# sd_tos.net
KiCad netlist of a schematic drawn in EAGLE
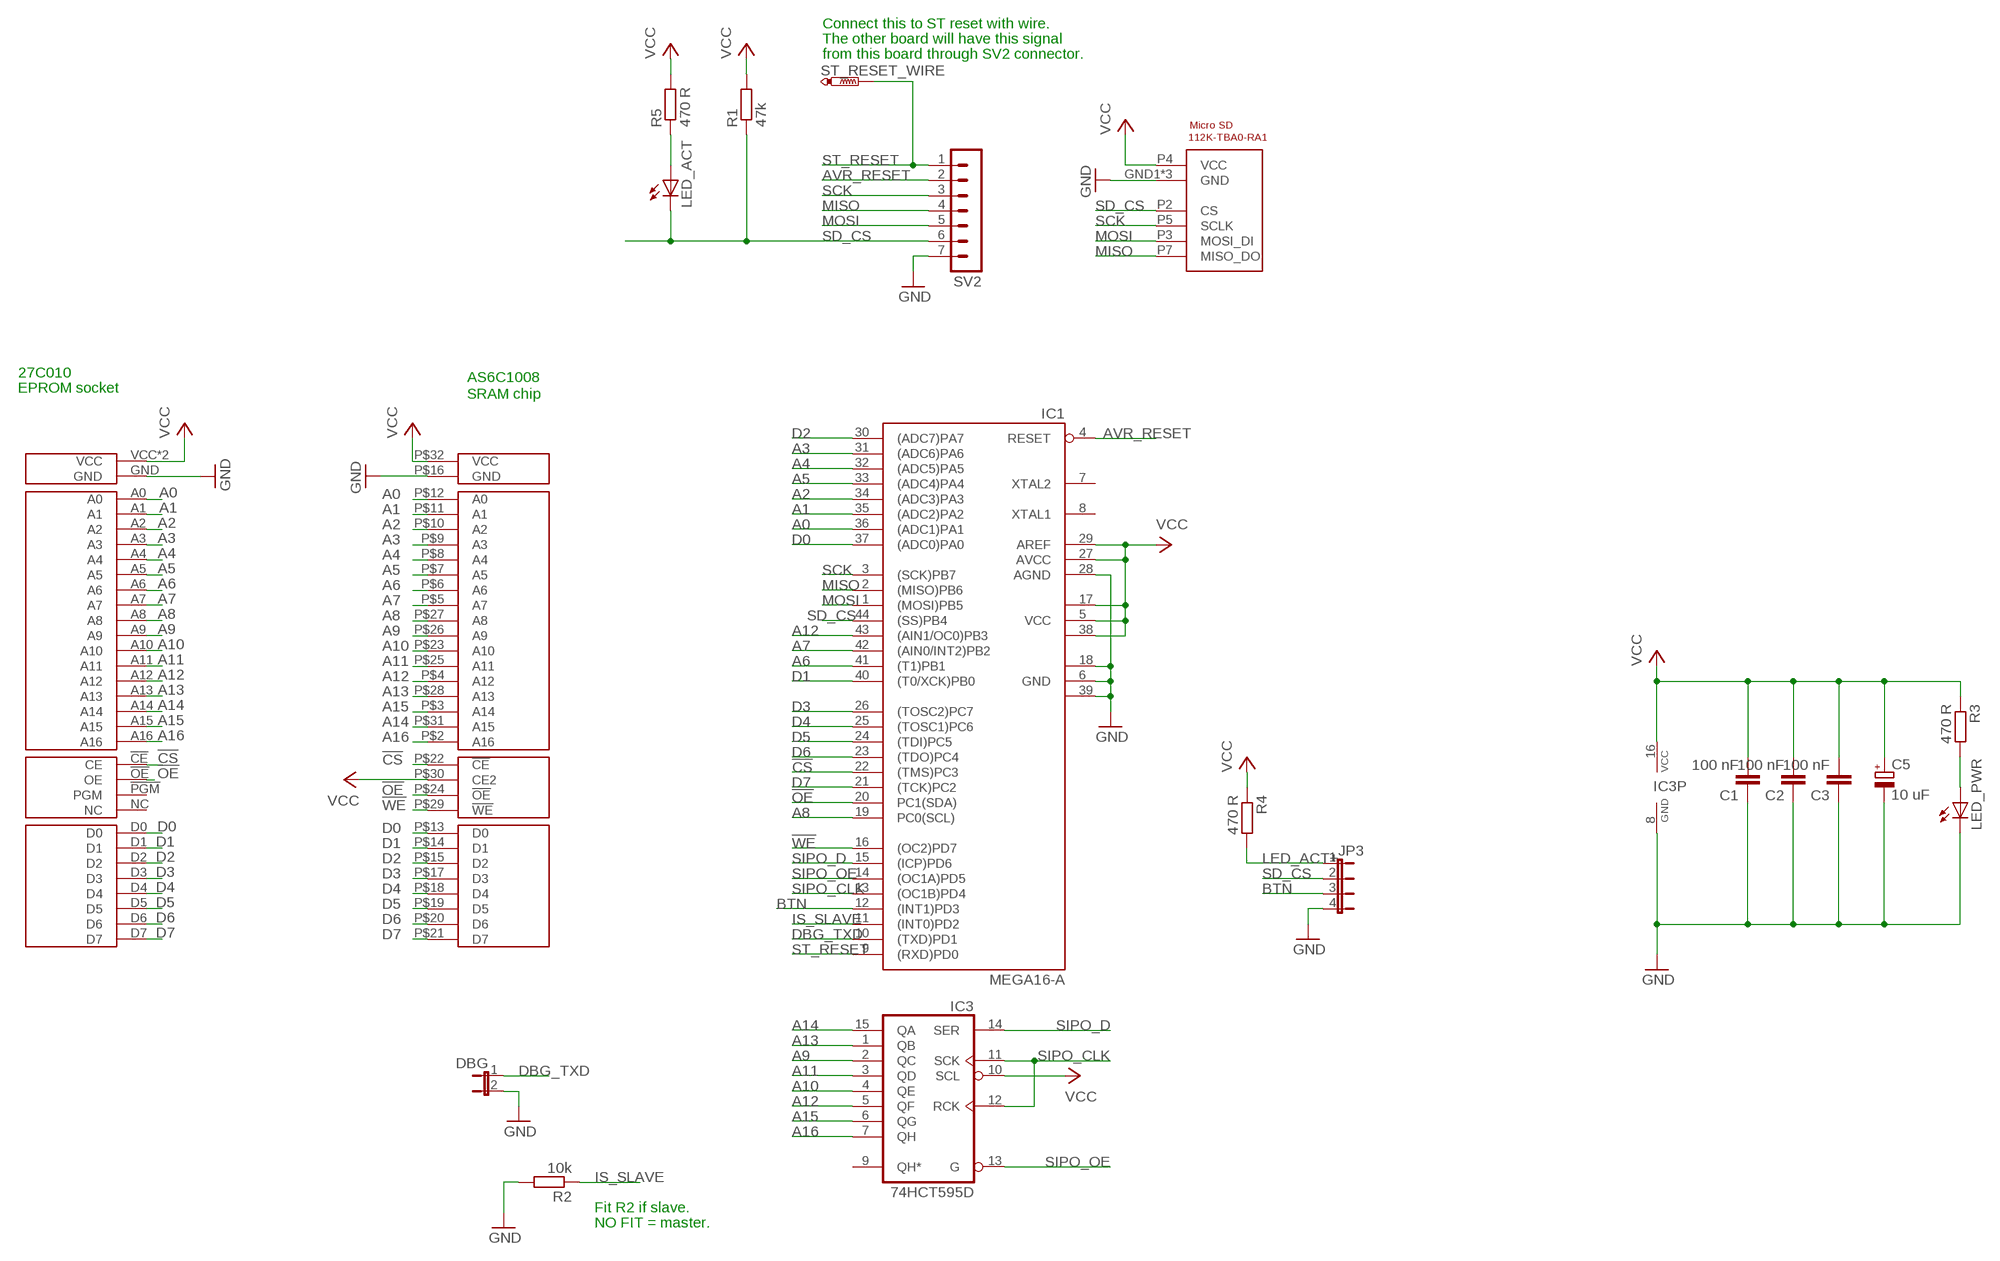
[diagram p0: schematic, sheet 1]

(export (version "E")
  (design (tool "Eeschema 10.0.6"))
  (components
    (comp (ref "C1")
      (value "100 nF")
      (footprint "eagle-import:C0603")
      (libsource (lib "eagle-import") (part "C-EUC0603"))
    )
    (comp (ref "C2")
      (value "100 nF")
      (footprint "eagle-import:C0603")
      (libsource (lib "eagle-import") (part "C-EUC0603"))
    )
    (comp (ref "C3")
      (value "100 nF")
      (footprint "eagle-import:C0603")
      (libsource (lib "eagle-import") (part "C-EUC0603"))
    )
    (comp (ref "C5")
      (value "10 uF")
      (footprint "eagle-import:SANYO-OSCON_SMD_B6")
      (libsource (lib "eagle-import") (part "CPOL-EUSANYO_SMD_B6"))
    )
    (comp (ref "DBG")
      (value "JP1E")
      (footprint "eagle-import:JP1")
      (libsource (lib "eagle-import") (part "JP1E"))
    )
    (comp (ref "IC1")
      (value "MEGA16-A")
      (footprint "eagle-import:TQFP44")
      (libsource (lib "eagle-import") (part "MEGA16-A"))
    )
    (comp (ref "IC3")
      (value "74HCT595D")
      (footprint "eagle-import:SO16")
      (libsource (lib "eagle-import") (part "74595DHCT"))
    )
    (comp (ref "JP3")
      (value "JP4E")
      (footprint "eagle-import:JP4")
      (libsource (lib "eagle-import") (part "JP4E"))
    )
    (comp (ref "LED_ACT")
      (value "LEDCHIP-LED0805")
      (footprint "eagle-import:CHIP-LED0805")
      (libsource (lib "eagle-import") (part "LEDCHIP-LED0805"))
    )
    (comp (ref "LED_PWR")
      (value "LEDCHIP-LED0805")
      (footprint "eagle-import:CHIP-LED0805")
      (libsource (lib "eagle-import") (part "LEDCHIP-LED0805"))
    )
    (comp (ref "R1")
      (value "47k")
      (footprint "eagle-import:R0603")
      (libsource (lib "eagle-import") (part "R-EU_R0603"))
    )
    (comp (ref "R2")
      (value "10k")
      (footprint "eagle-import:R0603")
      (libsource (lib "eagle-import") (part "R-EU_R0603"))
    )
    (comp (ref "R3")
      (value "470 R")
      (footprint "eagle-import:R0603")
      (libsource (lib "eagle-import") (part "R-EU_R0603"))
    )
    (comp (ref "R4")
      (value "470 R")
      (footprint "eagle-import:R0603")
      (libsource (lib "eagle-import") (part "R-EU_R0603"))
    )
    (comp (ref "R5")
      (value "470 R")
      (footprint "eagle-import:R0603")
      (libsource (lib "eagle-import") (part "R-EU_R0603"))
    )
    (comp (ref "ST_RESET_WIRE")
      (value "PTR1PAD1-13Y")
      (footprint "eagle-import:P1-13Y")
      (libsource (lib "eagle-import") (part "PTR1PAD1-13Y"))
    )
    (comp (ref "SV2")
      (value "MA07-1")
      (footprint "eagle-import:MA07-1")
      (libsource (lib "eagle-import") (part "MA07-1"))
    )
    (comp (ref "U$1")
      (value "27C010_BOTTOM_ONLY")
      (footprint "eagle-import:DIP32_BOTTOM_ONLY")
      (libsource (lib "eagle-import") (part "27C010_BOTTOM_ONLY"))
    )
    (comp (ref "U$2")
      (value "AS6C1008")
      (footprint "eagle-import:SOP32L")
      (libsource (lib "eagle-import") (part "AS6C1008"))
    )
    (comp (ref "U$3")
      (value "MICRO_SD")
      (footprint "eagle-import:MICRO_SD")
      (libsource (lib "eagle-import") (part "MICRO_SD"))
    )
  )
  (nets
    (net (code "1") (name "/A0") (class "Default")
      (node (ref "IC1") (pin "36") (pinfunction "(ADC1)PA1_36") (pintype "bidirectional"))
      (node (ref "U$1") (pin "A0") (pinfunction "A0_A0") (pintype "bidirectional"))
      (node (ref "U$2") (pin "P$12") (pinfunction "A0_P$12") (pintype "bidirectional"))
    )
    (net (code "2") (name "/A1") (class "Default")
      (node (ref "IC1") (pin "35") (pinfunction "(ADC2)PA2_35") (pintype "bidirectional"))
      (node (ref "U$1") (pin "A1") (pinfunction "A1_A1") (pintype "bidirectional"))
      (node (ref "U$2") (pin "P$11") (pinfunction "A1_P$11") (pintype "bidirectional"))
    )
    (net (code "3") (name "/A2") (class "Default")
      (node (ref "IC1") (pin "34") (pinfunction "(ADC3)PA3_34") (pintype "bidirectional"))
      (node (ref "U$1") (pin "A2") (pinfunction "A2_A2") (pintype "bidirectional"))
      (node (ref "U$2") (pin "P$10") (pinfunction "A2_P$10") (pintype "bidirectional"))
    )
    (net (code "4") (name "/A3") (class "Default")
      (node (ref "IC1") (pin "31") (pinfunction "(ADC6)PA6_31") (pintype "bidirectional"))
      (node (ref "U$1") (pin "A3") (pinfunction "A3_A3") (pintype "bidirectional"))
      (node (ref "U$2") (pin "P$9") (pinfunction "A3_P$9") (pintype "bidirectional"))
    )
    (net (code "5") (name "/A4") (class "Default")
      (node (ref "IC1") (pin "32") (pinfunction "(ADC5)PA5_32") (pintype "bidirectional"))
      (node (ref "U$1") (pin "A4") (pinfunction "A4_A4") (pintype "bidirectional"))
      (node (ref "U$2") (pin "P$8") (pinfunction "A4_P$8") (pintype "bidirectional"))
    )
    (net (code "6") (name "/A5") (class "Default")
      (node (ref "IC1") (pin "33") (pinfunction "(ADC4)PA4_33") (pintype "bidirectional"))
      (node (ref "U$1") (pin "A5") (pinfunction "A5_A5") (pintype "bidirectional"))
      (node (ref "U$2") (pin "P$7") (pinfunction "A5_P$7") (pintype "bidirectional"))
    )
    (net (code "7") (name "/A6") (class "Default")
      (node (ref "IC1") (pin "41") (pinfunction "(T1)PB1_41") (pintype "bidirectional"))
      (node (ref "U$1") (pin "A6") (pinfunction "A6_A6") (pintype "bidirectional"))
      (node (ref "U$2") (pin "P$6") (pinfunction "A6_P$6") (pintype "bidirectional"))
    )
    (net (code "8") (name "/A7") (class "Default")
      (node (ref "IC1") (pin "42") (pinfunction "(AIN0/INT2)PB2_42") (pintype "bidirectional"))
      (node (ref "U$1") (pin "A7") (pinfunction "A7_A7") (pintype "bidirectional"))
      (node (ref "U$2") (pin "P$5") (pinfunction "A7_P$5") (pintype "bidirectional"))
    )
    (net (code "9") (name "/A8") (class "Default")
      (node (ref "IC1") (pin "19") (pinfunction "PC0(SCL)_19") (pintype "bidirectional"))
      (node (ref "U$1") (pin "A8") (pinfunction "A8_A8") (pintype "bidirectional"))
      (node (ref "U$2") (pin "P$27") (pinfunction "A8_P$27") (pintype "bidirectional"))
    )
    (net (code "10") (name "/A9") (class "Default")
      (node (ref "IC3") (pin "2") (pinfunction "QC_2") (pintype "tri_state"))
      (node (ref "U$1") (pin "A9") (pinfunction "A9_A9") (pintype "bidirectional"))
      (node (ref "U$2") (pin "P$26") (pinfunction "A9_P$26") (pintype "bidirectional"))
    )
    (net (code "11") (name "/A10") (class "Default")
      (node (ref "IC3") (pin "4") (pinfunction "QE_4") (pintype "tri_state"))
      (node (ref "U$1") (pin "A10") (pinfunction "A10_A10") (pintype "bidirectional"))
      (node (ref "U$2") (pin "P$23") (pinfunction "A10_P$23") (pintype "bidirectional"))
    )
    (net (code "12") (name "/A11") (class "Default")
      (node (ref "IC3") (pin "3") (pinfunction "QD_3") (pintype "tri_state"))
      (node (ref "U$1") (pin "A11") (pinfunction "A11_A11") (pintype "bidirectional"))
      (node (ref "U$2") (pin "P$25") (pinfunction "A11_P$25") (pintype "bidirectional"))
    )
    (net (code "13") (name "/A12") (class "Default")
      (node (ref "IC1") (pin "43") (pinfunction "(AIN1/OC0)PB3_43") (pintype "bidirectional"))
      (node (ref "IC3") (pin "5") (pinfunction "QF_5") (pintype "tri_state"))
      (node (ref "U$1") (pin "A12") (pinfunction "A12_A12") (pintype "bidirectional"))
      (node (ref "U$2") (pin "P$4") (pinfunction "A12_P$4") (pintype "bidirectional"))
    )
    (net (code "14") (name "/A13") (class "Default")
      (node (ref "IC3") (pin "1") (pinfunction "QB_1") (pintype "tri_state"))
      (node (ref "U$1") (pin "A13") (pinfunction "A13_A13") (pintype "bidirectional"))
      (node (ref "U$2") (pin "P$28") (pinfunction "A13_P$28") (pintype "bidirectional"))
    )
    (net (code "15") (name "/A14") (class "Default")
      (node (ref "IC3") (pin "15") (pinfunction "QA_15") (pintype "tri_state"))
      (node (ref "U$1") (pin "A14") (pinfunction "A14_A14") (pintype "bidirectional"))
      (node (ref "U$2") (pin "P$31") (pinfunction "A15_P$31") (pintype "bidirectional"))
    )
    (net (code "16") (name "/A15") (class "Default")
      (node (ref "IC3") (pin "6") (pinfunction "QG_6") (pintype "tri_state"))
      (node (ref "U$1") (pin "A15") (pinfunction "A15_A15") (pintype "bidirectional"))
      (node (ref "U$2") (pin "P$3") (pinfunction "A14_P$3") (pintype "bidirectional"))
    )
    (net (code "17") (name "/A16") (class "Default")
      (node (ref "IC3") (pin "7") (pinfunction "QH_7") (pintype "tri_state"))
      (node (ref "U$1") (pin "A16") (pinfunction "A16_A16") (pintype "bidirectional"))
      (node (ref "U$2") (pin "P$2") (pinfunction "A16_P$2") (pintype "bidirectional"))
    )
    (net (code "18") (name "/AVR_RESET") (class "Default")
      (node (ref "IC1") (pin "4") (pinfunction "RESET_4") (pintype "input"))
      (node (ref "SV2") (pin "2") (pinfunction "2_2") (pintype "passive"))
    )
    (net (code "19") (name "/BTN") (class "Default")
      (node (ref "IC1") (pin "12") (pinfunction "(INT1)PD3_12") (pintype "bidirectional"))
      (node (ref "JP3") (pin "3") (pinfunction "3_3") (pintype "passive"))
    )
    (net (code "20") (name "/D0") (class "Default")
      (node (ref "IC1") (pin "37") (pinfunction "(ADC0)PA0_37") (pintype "bidirectional"))
      (node (ref "U$1") (pin "D0") (pinfunction "D0_D0") (pintype "bidirectional"))
      (node (ref "U$2") (pin "P$13") (pinfunction "D0_P$13") (pintype "bidirectional"))
    )
    (net (code "21") (name "/D1") (class "Default")
      (node (ref "IC1") (pin "40") (pinfunction "(T0/XCK)PB0_40") (pintype "bidirectional"))
      (node (ref "U$1") (pin "D1") (pinfunction "D1_D1") (pintype "bidirectional"))
      (node (ref "U$2") (pin "P$14") (pinfunction "D1_P$14") (pintype "bidirectional"))
    )
    (net (code "22") (name "/D2") (class "Default")
      (node (ref "IC1") (pin "30") (pinfunction "(ADC7)PA7_30") (pintype "bidirectional"))
      (node (ref "U$1") (pin "D2") (pinfunction "D2_D2") (pintype "bidirectional"))
      (node (ref "U$2") (pin "P$15") (pinfunction "D2_P$15") (pintype "bidirectional"))
    )
    (net (code "23") (name "/D3") (class "Default")
      (node (ref "IC1") (pin "26") (pinfunction "(TOSC2)PC7_26") (pintype "bidirectional"))
      (node (ref "U$1") (pin "D3") (pinfunction "D3_D3") (pintype "bidirectional"))
      (node (ref "U$2") (pin "P$17") (pinfunction "D3_P$17") (pintype "bidirectional"))
    )
    (net (code "24") (name "/D4") (class "Default")
      (node (ref "IC1") (pin "25") (pinfunction "(TOSC1)PC6_25") (pintype "bidirectional"))
      (node (ref "U$1") (pin "D4") (pinfunction "D4_D4") (pintype "bidirectional"))
      (node (ref "U$2") (pin "P$18") (pinfunction "D4_P$18") (pintype "bidirectional"))
    )
    (net (code "25") (name "/D5") (class "Default")
      (node (ref "IC1") (pin "24") (pinfunction "(TDI)PC5_24") (pintype "bidirectional"))
      (node (ref "U$1") (pin "D5") (pinfunction "D5_D5") (pintype "bidirectional"))
      (node (ref "U$2") (pin "P$19") (pinfunction "D5_P$19") (pintype "bidirectional"))
    )
    (net (code "26") (name "/D6") (class "Default")
      (node (ref "IC1") (pin "23") (pinfunction "(TDO)PC4_23") (pintype "bidirectional"))
      (node (ref "U$1") (pin "D6") (pinfunction "D6_D6") (pintype "bidirectional"))
      (node (ref "U$2") (pin "P$20") (pinfunction "D6_P$20") (pintype "bidirectional"))
    )
    (net (code "27") (name "/D7") (class "Default")
      (node (ref "IC1") (pin "21") (pinfunction "(TCK)PC2_21") (pintype "bidirectional"))
      (node (ref "U$1") (pin "D7") (pinfunction "D7_D7") (pintype "bidirectional"))
      (node (ref "U$2") (pin "P$21") (pinfunction "D7_P$21") (pintype "bidirectional"))
    )
    (net (code "28") (name "/DBG_TXD") (class "Default")
      (node (ref "DBG") (pin "1") (pinfunction "1_1") (pintype "passive"))
      (node (ref "IC1") (pin "10") (pinfunction "(TXD)PD1_10") (pintype "bidirectional"))
    )
    (net (code "29") (name "/IS_SLAVE") (class "Default")
      (node (ref "IC1") (pin "11") (pinfunction "(INT0)PD2_11") (pintype "bidirectional"))
      (node (ref "R2") (pin "1") (pinfunction "1_1") (pintype "passive"))
    )
    (net (code "30") (name "/LED_ACT+") (class "Default")
      (node (ref "JP3") (pin "1") (pinfunction "1_1") (pintype "passive"))
      (node (ref "R4") (pin "2") (pinfunction "2_2") (pintype "passive"))
    )
    (net (code "31") (name "/MISO") (class "Default")
      (node (ref "IC1") (pin "2") (pinfunction "(MISO)PB6_2") (pintype "bidirectional"))
      (node (ref "SV2") (pin "4") (pinfunction "4_4") (pintype "passive"))
      (node (ref "U$3") (pin "P7") (pinfunction "MISO_DO_P7") (pintype "output"))
    )
    (net (code "32") (name "/MOSI") (class "Default")
      (node (ref "IC1") (pin "1") (pinfunction "(MOSI)PB5_1") (pintype "bidirectional"))
      (node (ref "SV2") (pin "5") (pinfunction "5_5") (pintype "passive"))
      (node (ref "U$3") (pin "P3") (pinfunction "MOSI_DI_P3") (pintype "input"))
    )
    (net (code "33") (name "/SCK") (class "Default")
      (node (ref "IC1") (pin "3") (pinfunction "(SCK)PB7_3") (pintype "bidirectional"))
      (node (ref "SV2") (pin "3") (pinfunction "3_3") (pintype "passive"))
      (node (ref "U$3") (pin "P5") (pinfunction "SCLK_P5") (pintype "input"))
    )
    (net (code "34") (name "/SD_CS") (class "Default")
      (node (ref "IC1") (pin "44") (pinfunction "(SS)PB4_44") (pintype "bidirectional"))
      (node (ref "JP3") (pin "2") (pinfunction "2_2") (pintype "passive"))
      (node (ref "LED_ACT") (pin "C") (pinfunction "C_C") (pintype "passive"))
      (node (ref "R1") (pin "1") (pinfunction "1_1") (pintype "passive"))
      (node (ref "SV2") (pin "6") (pinfunction "6_6") (pintype "passive"))
      (node (ref "U$3") (pin "P2") (pinfunction "CS_P2") (pintype "input"))
    )
    (net (code "35") (name "/SIPO_CLK") (class "Default")
      (node (ref "IC1") (pin "13") (pinfunction "(OC1B)PD4_13") (pintype "bidirectional"))
      (node (ref "IC3") (pin "11") (pinfunction "SCK_11") (pintype "input"))
      (node (ref "IC3") (pin "12") (pinfunction "RCK_12") (pintype "input"))
    )
    (net (code "36") (name "/SIPO_D") (class "Default")
      (node (ref "IC1") (pin "15") (pinfunction "(ICP)PD6_15") (pintype "bidirectional"))
      (node (ref "IC3") (pin "14") (pinfunction "SER_14") (pintype "input"))
    )
    (net (code "37") (name "/SIPO_OE") (class "Default")
      (node (ref "IC1") (pin "14") (pinfunction "(OC1A)PD5_14") (pintype "bidirectional"))
      (node (ref "IC3") (pin "13") (pinfunction "G_13") (pintype "input"))
    )
    (net (code "38") (name "/ST_RESET") (class "Default")
      (node (ref "IC1") (pin "9") (pinfunction "(RXD)PD0_9") (pintype "bidirectional"))
      (node (ref "ST_RESET_WIRE") (pin "TP") (pinfunction "TP_TP") (pintype "input"))
      (node (ref "SV2") (pin "1") (pinfunction "1_1") (pintype "passive"))
    )
    (net (code "39") (name "/~{CS}") (class "Default")
      (node (ref "IC1") (pin "22") (pinfunction "(TMS)PC3_22") (pintype "bidirectional"))
      (node (ref "U$1") (pin "!CE") (pinfunction "CE_!CE") (pintype "bidirectional"))
      (node (ref "U$2") (pin "P$22") (pinfunction "~{CE}_P$22") (pintype "bidirectional"))
    )
    (net (code "40") (name "/~{OE}") (class "Default")
      (node (ref "IC1") (pin "20") (pinfunction "PC1(SDA)_20") (pintype "bidirectional"))
      (node (ref "U$1") (pin "!OE") (pinfunction "OE_!OE") (pintype "bidirectional"))
      (node (ref "U$2") (pin "P$24") (pinfunction "~{OE}_P$24") (pintype "bidirectional"))
    )
    (net (code "41") (name "/~{WE}") (class "Default")
      (node (ref "IC1") (pin "16") (pinfunction "(OC2)PD7_16") (pintype "bidirectional"))
      (node (ref "U$2") (pin "P$29") (pinfunction "~{WE}_P$29") (pintype "bidirectional"))
    )
    (net (code "42") (name "GND") (class "Default")
      (node (ref "C1") (pin "1") (pinfunction "1_1") (pintype "passive"))
      (node (ref "C2") (pin "1") (pinfunction "1_1") (pintype "passive"))
      (node (ref "C3") (pin "1") (pinfunction "1_1") (pintype "passive"))
      (node (ref "C5") (pin "-") (pinfunction "-_-") (pintype "passive"))
      (node (ref "DBG") (pin "2") (pinfunction "2_2") (pintype "passive"))
      (node (ref "IC1") (pin "18") (pinfunction "GND1_18") (pintype "power_in"))
      (node (ref "IC1") (pin "28") (pinfunction "AGND_28") (pintype "power_in"))
      (node (ref "IC1") (pin "39") (pinfunction "GND2_39") (pintype "power_in"))
      (node (ref "IC1") (pin "6") (pinfunction "GND_6") (pintype "power_in"))
      (node (ref "IC3") (pin "8") (pinfunction "GND_8") (pintype "power_in"))
      (node (ref "JP3") (pin "4") (pinfunction "4_4") (pintype "passive"))
      (node (ref "LED_PWR") (pin "C") (pinfunction "C_C") (pintype "passive"))
      (node (ref "R2") (pin "2") (pinfunction "2_2") (pintype "passive"))
      (node (ref "SV2") (pin "7") (pinfunction "7_7") (pintype "passive"))
      (node (ref "U$1") (pin "GND") (pinfunction "GND_GND") (pintype "bidirectional"))
      (node (ref "U$2") (pin "P$16") (pinfunction "GND_P$16") (pintype "bidirectional"))
      (node (ref "U$3") (pin "GND1") (pinfunction "GND_GND1") (pintype "power_in"))
      (node (ref "U$3") (pin "GND2") (pinfunction "GND_GND2") (pintype "power_in"))
      (node (ref "U$3") (pin "P6") (pinfunction "GND_P6") (pintype "power_in"))
    )
    (net (code "43") (name "Net-(LED_ACT-PadA)") (class "Default")
      (node (ref "LED_ACT") (pin "A") (pinfunction "A_A") (pintype "passive"))
      (node (ref "R5") (pin "1") (pinfunction "1_1") (pintype "passive"))
    )
    (net (code "44") (name "Net-(LED_PWR-PadA)") (class "Default")
      (node (ref "LED_PWR") (pin "A") (pinfunction "A_A") (pintype "passive"))
      (node (ref "R3") (pin "2") (pinfunction "2_2") (pintype "passive"))
    )
    (net (code "45") (name "VCC") (class "Default")
      (node (ref "C1") (pin "2") (pinfunction "2_2") (pintype "passive"))
      (node (ref "C2") (pin "2") (pinfunction "2_2") (pintype "passive"))
      (node (ref "C3") (pin "2") (pinfunction "2_2") (pintype "passive"))
      (node (ref "C5") (pin "+") (pinfunction "+_+") (pintype "passive"))
      (node (ref "IC1") (pin "17") (pinfunction "VCC1_17") (pintype "power_in"))
      (node (ref "IC1") (pin "27") (pinfunction "AVCC_27") (pintype "power_in"))
      (node (ref "IC1") (pin "29") (pinfunction "AREF_29") (pintype "power_in"))
      (node (ref "IC1") (pin "38") (pinfunction "VCC2_38") (pintype "power_in"))
      (node (ref "IC1") (pin "5") (pinfunction "VCC_5") (pintype "power_in"))
      (node (ref "IC3") (pin "10") (pinfunction "SCL_10") (pintype "input"))
      (node (ref "IC3") (pin "16") (pinfunction "VCC_16") (pintype "power_in"))
      (node (ref "R1") (pin "2") (pinfunction "2_2") (pintype "passive"))
      (node (ref "R3") (pin "1") (pinfunction "1_1") (pintype "passive"))
      (node (ref "R4") (pin "1") (pinfunction "1_1") (pintype "passive"))
      (node (ref "R5") (pin "2") (pinfunction "2_2") (pintype "passive"))
      (node (ref "U$1") (pin "VCC") (pinfunction "VCC_VCC") (pintype "bidirectional"))
      (node (ref "U$1") (pin "VPP") (pinfunction "VCC_VPP") (pintype "bidirectional"))
      (node (ref "U$2") (pin "P$30") (pinfunction "CE2_P$30") (pintype "bidirectional"))
      (node (ref "U$2") (pin "P$32") (pinfunction "VCC_P$32") (pintype "bidirectional"))
      (node (ref "U$3") (pin "P4") (pinfunction "VCC_P4") (pintype "power_in"))
    )
    (net (code "46") (name "unconnected-(IC1-XTAL1-Pad8)") (class "Default")
      (node (ref "IC1") (pin "8") (pinfunction "XTAL1_8") (pintype "bidirectional"))
    )
    (net (code "47") (name "unconnected-(IC1-XTAL2-Pad7)") (class "Default")
      (node (ref "IC1") (pin "7") (pinfunction "XTAL2_7") (pintype "bidirectional"))
    )
    (net (code "48") (name "unconnected-(IC3A-QH*-Pad9)") (class "Default")
      (node (ref "IC3") (pin "9") (pinfunction "QH*_9") (pintype "tri_state"))
    )
    (net (code "49") (name "unconnected-(U$1-PGM-Pad!PGM)") (class "Default")
      (node (ref "U$1") (pin "!PGM") (pinfunction "PGM_!PGM") (pintype "bidirectional"))
    )
    (net (code "50") (name "unconnected-(U$1-PadNC)") (class "Default")
      (node (ref "U$1") (pin "NC") (pinfunction "NC_NC") (pintype "bidirectional"))
    )
  )
)
